# digilent.net
KiCad netlist of a schematic drawn in EAGLE
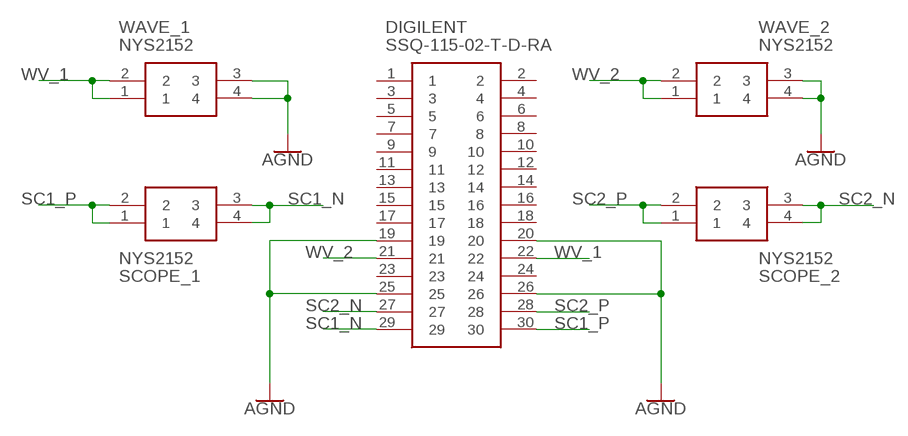
[diagram p0: schematic, sheet 1]

(export (version "E")
  (design (tool "Eeschema 10.0.6"))
  (components
    (comp (ref "DIGILENT")
      (value "SSQ-115-02-T-D-RA")
      (footprint "eagle-import:RHDRRA30W64P254_2X15_3861X851X")
      (fields (field (name "MOUSER_PART_NUMBER") "200-SSQ11502TDRA"))
      (libsource (lib "eagle-import") (part "SSQ-115-02-T-D-RA"))
    )
    (comp (ref "SCOPE_1")
      (value "NYS2152")
      (footprint "eagle-import:NYS2152")
      (fields (field (name "MOUSER_PART_NUMBER") "568-NYS215/2"))
      (libsource (lib "eagle-import") (part "NYS2152"))
    )
    (comp (ref "SCOPE_2")
      (value "NYS2152")
      (footprint "eagle-import:NYS2152")
      (fields (field (name "MOUSER_PART_NUMBER") "568-NYS215/2"))
      (libsource (lib "eagle-import") (part "NYS2152"))
    )
    (comp (ref "WAVE_1")
      (value "NYS2152")
      (footprint "eagle-import:NYS2152")
      (fields (field (name "MOUSER_PART_NUMBER") "568-NYS215/2"))
      (libsource (lib "eagle-import") (part "NYS2152"))
    )
    (comp (ref "WAVE_2")
      (value "NYS2152")
      (footprint "eagle-import:NYS2152")
      (fields (field (name "MOUSER_PART_NUMBER") "568-NYS215/2"))
      (libsource (lib "eagle-import") (part "NYS2152"))
    )
  )
  (nets
    (net (code "1") (name "/SC1_N") (class "Default")
      (node (ref "DIGILENT") (pin "29") (pinfunction "29_29") (pintype "bidirectional"))
      (node (ref "SCOPE_1") (pin "3") (pinfunction "3_3") (pintype "bidirectional"))
      (node (ref "SCOPE_1") (pin "4") (pinfunction "4_4") (pintype "bidirectional"))
    )
    (net (code "2") (name "/SC1_P") (class "Default")
      (node (ref "DIGILENT") (pin "30") (pinfunction "30_30") (pintype "bidirectional"))
      (node (ref "SCOPE_1") (pin "1") (pinfunction "1_1") (pintype "bidirectional"))
      (node (ref "SCOPE_1") (pin "2") (pinfunction "2_2") (pintype "bidirectional"))
    )
    (net (code "3") (name "/SC2_N") (class "Default")
      (node (ref "DIGILENT") (pin "27") (pinfunction "27_27") (pintype "bidirectional"))
      (node (ref "SCOPE_2") (pin "3") (pinfunction "3_3") (pintype "bidirectional"))
      (node (ref "SCOPE_2") (pin "4") (pinfunction "4_4") (pintype "bidirectional"))
    )
    (net (code "4") (name "/SC2_P") (class "Default")
      (node (ref "DIGILENT") (pin "28") (pinfunction "28_28") (pintype "bidirectional"))
      (node (ref "SCOPE_2") (pin "1") (pinfunction "1_1") (pintype "bidirectional"))
      (node (ref "SCOPE_2") (pin "2") (pinfunction "2_2") (pintype "bidirectional"))
    )
    (net (code "5") (name "/WV_1") (class "Default")
      (node (ref "DIGILENT") (pin "22") (pinfunction "22_22") (pintype "bidirectional"))
      (node (ref "WAVE_1") (pin "1") (pinfunction "1_1") (pintype "bidirectional"))
      (node (ref "WAVE_1") (pin "2") (pinfunction "2_2") (pintype "bidirectional"))
    )
    (net (code "6") (name "/WV_2") (class "Default")
      (node (ref "DIGILENT") (pin "21") (pinfunction "21_21") (pintype "bidirectional"))
      (node (ref "WAVE_2") (pin "1") (pinfunction "1_1") (pintype "bidirectional"))
      (node (ref "WAVE_2") (pin "2") (pinfunction "2_2") (pintype "bidirectional"))
    )
    (net (code "7") (name "AGND") (class "Default")
      (node (ref "DIGILENT") (pin "19") (pinfunction "19_19") (pintype "bidirectional"))
      (node (ref "DIGILENT") (pin "20") (pinfunction "20_20") (pintype "bidirectional"))
      (node (ref "DIGILENT") (pin "25") (pinfunction "25_25") (pintype "bidirectional"))
      (node (ref "DIGILENT") (pin "26") (pinfunction "26_26") (pintype "bidirectional"))
      (node (ref "WAVE_1") (pin "3") (pinfunction "3_3") (pintype "bidirectional"))
      (node (ref "WAVE_1") (pin "4") (pinfunction "4_4") (pintype "bidirectional"))
      (node (ref "WAVE_2") (pin "3") (pinfunction "3_3") (pintype "bidirectional"))
      (node (ref "WAVE_2") (pin "4") (pinfunction "4_4") (pintype "bidirectional"))
    )
    (net (code "8") (name "unconnected-(DIGILENT-Pad1)") (class "Default")
      (node (ref "DIGILENT") (pin "1") (pinfunction "1_1") (pintype "bidirectional"))
    )
    (net (code "9") (name "unconnected-(DIGILENT-Pad2)") (class "Default")
      (node (ref "DIGILENT") (pin "2") (pinfunction "2_2") (pintype "bidirectional"))
    )
    (net (code "10") (name "unconnected-(DIGILENT-Pad3)") (class "Default")
      (node (ref "DIGILENT") (pin "3") (pinfunction "3_3") (pintype "bidirectional"))
    )
    (net (code "11") (name "unconnected-(DIGILENT-Pad4)") (class "Default")
      (node (ref "DIGILENT") (pin "4") (pinfunction "4_4") (pintype "bidirectional"))
    )
    (net (code "12") (name "unconnected-(DIGILENT-Pad5)") (class "Default")
      (node (ref "DIGILENT") (pin "5") (pinfunction "5_5") (pintype "bidirectional"))
    )
    (net (code "13") (name "unconnected-(DIGILENT-Pad6)") (class "Default")
      (node (ref "DIGILENT") (pin "6") (pinfunction "6_6") (pintype "bidirectional"))
    )
    (net (code "14") (name "unconnected-(DIGILENT-Pad7)") (class "Default")
      (node (ref "DIGILENT") (pin "7") (pinfunction "7_7") (pintype "bidirectional"))
    )
    (net (code "15") (name "unconnected-(DIGILENT-Pad8)") (class "Default")
      (node (ref "DIGILENT") (pin "8") (pinfunction "8_8") (pintype "bidirectional"))
    )
    (net (code "16") (name "unconnected-(DIGILENT-Pad9)") (class "Default")
      (node (ref "DIGILENT") (pin "9") (pinfunction "9_9") (pintype "bidirectional"))
    )
    (net (code "17") (name "unconnected-(DIGILENT-Pad10)") (class "Default")
      (node (ref "DIGILENT") (pin "10") (pinfunction "10_10") (pintype "bidirectional"))
    )
    (net (code "18") (name "unconnected-(DIGILENT-Pad11)") (class "Default")
      (node (ref "DIGILENT") (pin "11") (pinfunction "11_11") (pintype "bidirectional"))
    )
    (net (code "19") (name "unconnected-(DIGILENT-Pad12)") (class "Default")
      (node (ref "DIGILENT") (pin "12") (pinfunction "12_12") (pintype "bidirectional"))
    )
    (net (code "20") (name "unconnected-(DIGILENT-Pad13)") (class "Default")
      (node (ref "DIGILENT") (pin "13") (pinfunction "13_13") (pintype "bidirectional"))
    )
    (net (code "21") (name "unconnected-(DIGILENT-Pad14)") (class "Default")
      (node (ref "DIGILENT") (pin "14") (pinfunction "14_14") (pintype "bidirectional"))
    )
    (net (code "22") (name "unconnected-(DIGILENT-Pad15)") (class "Default")
      (node (ref "DIGILENT") (pin "15") (pinfunction "15_15") (pintype "bidirectional"))
    )
    (net (code "23") (name "unconnected-(DIGILENT-Pad16)") (class "Default")
      (node (ref "DIGILENT") (pin "16") (pinfunction "16_16") (pintype "bidirectional"))
    )
    (net (code "24") (name "unconnected-(DIGILENT-Pad17)") (class "Default")
      (node (ref "DIGILENT") (pin "17") (pinfunction "17_17") (pintype "bidirectional"))
    )
    (net (code "25") (name "unconnected-(DIGILENT-Pad18)") (class "Default")
      (node (ref "DIGILENT") (pin "18") (pinfunction "18_18") (pintype "bidirectional"))
    )
    (net (code "26") (name "unconnected-(DIGILENT-Pad23)") (class "Default")
      (node (ref "DIGILENT") (pin "23") (pinfunction "23_23") (pintype "bidirectional"))
    )
    (net (code "27") (name "unconnected-(DIGILENT-Pad24)") (class "Default")
      (node (ref "DIGILENT") (pin "24") (pinfunction "24_24") (pintype "bidirectional"))
    )
  )
)
